# RTC_DS1307.net
KiCad netlist of a schematic drawn in EAGLE
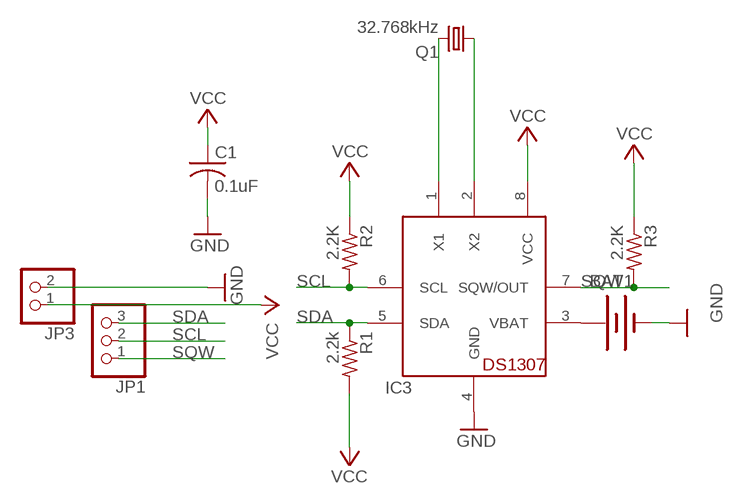
[diagram p0: schematic, sheet 1]

(export (version "E")
  (design (tool "Eeschema 10.0.6"))
  (components
    (comp (ref "BAT1")
      (value "BATTERY20PTH")
      (footprint "eagle-import:BATTCOM_20MM_PTH")
      (libsource (lib "eagle-import") (part "BATTERY20PTH"))
    )
    (comp (ref "C1")
      (value "0.1uF")
      (footprint "eagle-import:C025-025X050")
      (libsource (lib "eagle-import") (part "C-US025-025X050"))
    )
    (comp (ref "IC3")
      (value "DS1307")
      (footprint "eagle-import:DIL08")
      (libsource (lib "eagle-import") (part "DS1307"))
    )
    (comp (ref "JP1")
      (value "PINHD-1X3")
      (footprint "eagle-import:1X03")
      (libsource (lib "eagle-import") (part "PINHD-1X3"))
    )
    (comp (ref "JP3")
      (value "PINHD-1X2")
      (footprint "eagle-import:1X02")
      (libsource (lib "eagle-import") (part "PINHD-1X2"))
    )
    (comp (ref "Q1")
      (value "32.768kHz")
      (footprint "eagle-import:TC26H")
      (libsource (lib "eagle-import") (part "CRYSTALTC26H"))
    )
    (comp (ref "R1")
      (value "2.2k")
      (footprint "eagle-import:0207_10")
      (libsource (lib "eagle-import") (part "R-US_0207/10"))
    )
    (comp (ref "R2")
      (value "2.2K")
      (footprint "eagle-import:0207_10")
      (libsource (lib "eagle-import") (part "R-US_0207/10"))
    )
    (comp (ref "R3")
      (value "2.2K")
      (footprint "eagle-import:0207_10")
      (libsource (lib "eagle-import") (part "R-US_0207/10"))
    )
  )
  (nets
    (net (code "1") (name "/SCL") (class "Default")
      (node (ref "IC3") (pin "6") (pinfunction "SCL_6") (pintype "bidirectional"))
      (node (ref "JP1") (pin "2") (pinfunction "2_2") (pintype "passive"))
      (node (ref "R2") (pin "2") (pinfunction "2_2") (pintype "passive"))
    )
    (net (code "2") (name "/SDA") (class "Default")
      (node (ref "IC3") (pin "5") (pinfunction "SDA_5") (pintype "bidirectional"))
      (node (ref "JP1") (pin "3") (pinfunction "3_3") (pintype "passive"))
      (node (ref "R1") (pin "1") (pinfunction "1_1") (pintype "passive"))
    )
    (net (code "3") (name "/SQW") (class "Default")
      (node (ref "IC3") (pin "7") (pinfunction "SQW/OUT_7") (pintype "bidirectional"))
      (node (ref "JP1") (pin "1") (pinfunction "1_1") (pintype "passive"))
      (node (ref "R3") (pin "2") (pinfunction "2_2") (pintype "passive"))
    )
    (net (code "4") (name "GND") (class "Default")
      (node (ref "BAT1") (pin "2") (pinfunction "-_2") (pintype "power_in"))
      (node (ref "C1") (pin "2") (pinfunction "2_2") (pintype "passive"))
      (node (ref "IC3") (pin "4") (pinfunction "GND_4") (pintype "power_in"))
      (node (ref "JP3") (pin "2") (pinfunction "2_2") (pintype "passive"))
    )
    (net (code "5") (name "Net-(BAT1-+)") (class "Default")
      (node (ref "BAT1") (pin "1") (pinfunction "+_1") (pintype "power_in"))
      (node (ref "IC3") (pin "3") (pinfunction "VBAT_3") (pintype "power_in"))
    )
    (net (code "6") (name "Net-(IC3-X1)") (class "Default")
      (node (ref "IC3") (pin "1") (pinfunction "X1_1") (pintype "passive"))
      (node (ref "Q1") (pin "2") (pinfunction "2_2") (pintype "passive"))
    )
    (net (code "7") (name "Net-(IC3-X2)") (class "Default")
      (node (ref "IC3") (pin "2") (pinfunction "X2_2") (pintype "passive"))
      (node (ref "Q1") (pin "1") (pinfunction "1_1") (pintype "passive"))
    )
    (net (code "8") (name "VCC") (class "Default")
      (node (ref "C1") (pin "1") (pinfunction "1_1") (pintype "passive"))
      (node (ref "IC3") (pin "8") (pinfunction "VCC_8") (pintype "power_in"))
      (node (ref "JP3") (pin "1") (pinfunction "1_1") (pintype "passive"))
      (node (ref "R1") (pin "2") (pinfunction "2_2") (pintype "passive"))
      (node (ref "R2") (pin "1") (pinfunction "1_1") (pintype "passive"))
      (node (ref "R3") (pin "1") (pinfunction "1_1") (pintype "passive"))
    )
  )
)
